# ControlModule.net
KiCad netlist of a schematic drawn in EAGLE
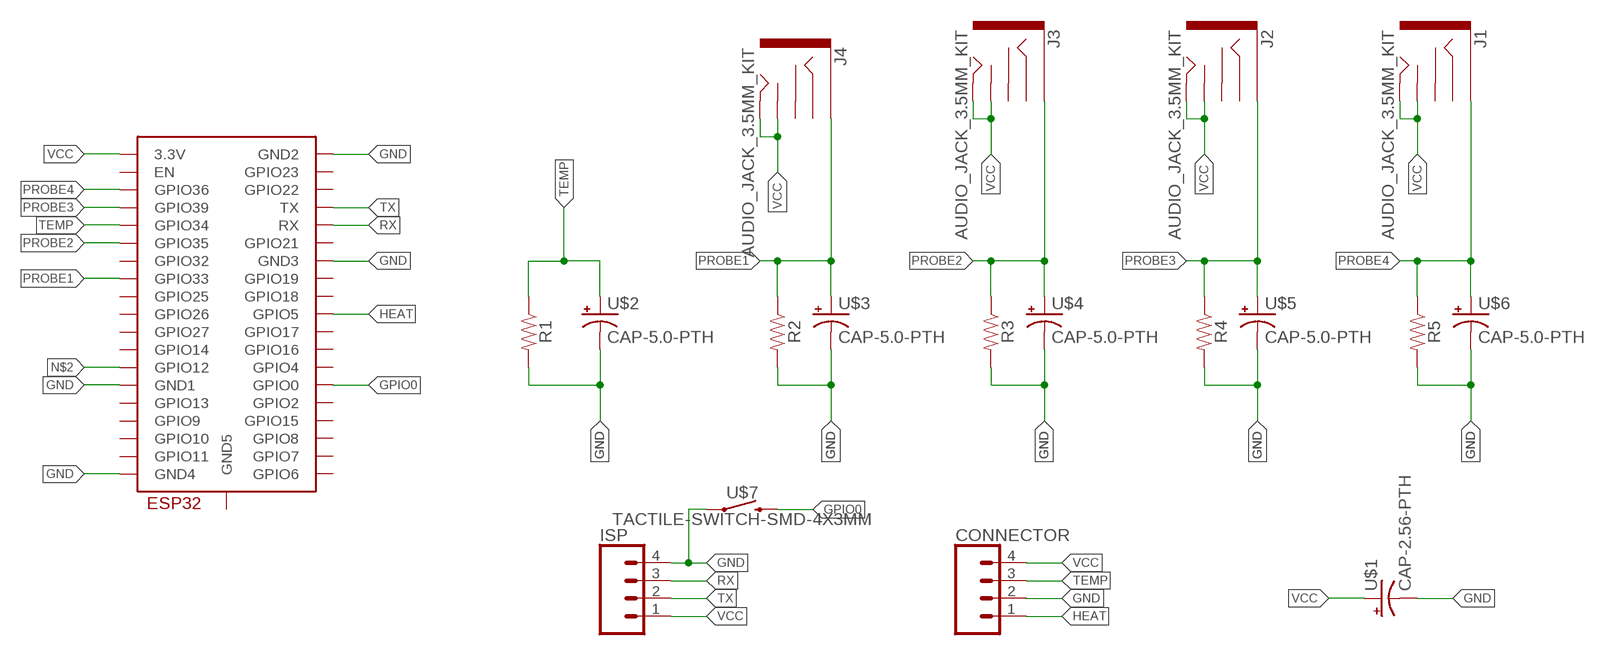
[diagram p0: schematic, sheet 1]

(export (version "E")
  (design (tool "Eeschema 10.0.6"))
  (components
    (comp (ref "CONNECTOR")
      (value "CONN_04PTH")
      (footprint "eagle-import:1X04")
      (libsource (lib "eagle-import") (part "CONN_04PTH"))
    )
    (comp (ref "ISP")
      (value "CONN_04PTH")
      (footprint "eagle-import:1X04")
      (libsource (lib "eagle-import") (part "CONN_04PTH"))
    )
    (comp (ref "J1")
      (value "AUDIO_JACK_3.5MM_KIT")
      (footprint "eagle-import:AUDIO-JACK-KIT")
      (libsource (lib "eagle-import") (part "AUDIO_JACK_3.5MM_KIT"))
    )
    (comp (ref "J2")
      (value "AUDIO_JACK_3.5MM_KIT")
      (footprint "eagle-import:AUDIO-JACK-KIT")
      (libsource (lib "eagle-import") (part "AUDIO_JACK_3.5MM_KIT"))
    )
    (comp (ref "J3")
      (value "AUDIO_JACK_3.5MM_KIT")
      (footprint "eagle-import:AUDIO-JACK-KIT")
      (libsource (lib "eagle-import") (part "AUDIO_JACK_3.5MM_KIT"))
    )
    (comp (ref "J4")
      (value "AUDIO_JACK_3.5MM_KIT")
      (footprint "eagle-import:AUDIO-JACK-KIT")
      (libsource (lib "eagle-import") (part "AUDIO_JACK_3.5MM_KIT"))
    )
    (comp (ref "R1")
      (value "RESISTOR0805")
      (footprint "eagle-import:0805")
      (libsource (lib "eagle-import") (part "RESISTOR0805"))
    )
    (comp (ref "R2")
      (value "RESISTOR0805")
      (footprint "eagle-import:0805")
      (libsource (lib "eagle-import") (part "RESISTOR0805"))
    )
    (comp (ref "R3")
      (value "RESISTOR0805")
      (footprint "eagle-import:0805")
      (libsource (lib "eagle-import") (part "RESISTOR0805"))
    )
    (comp (ref "R4")
      (value "RESISTOR0805")
      (footprint "eagle-import:0805")
      (libsource (lib "eagle-import") (part "RESISTOR0805"))
    )
    (comp (ref "R5")
      (value "RESISTOR0805")
      (footprint "eagle-import:0805")
      (libsource (lib "eagle-import") (part "RESISTOR0805"))
    )
    (comp (ref "U$1")
      (value "CAP-2.56-PTH")
      (footprint "eagle-import:CAP-PTH-2.5MM-5MM")
      (libsource (lib "eagle-import") (part "CAP-2.56-PTH"))
    )
    (comp (ref "U$2")
      (value "CAP-5.0-PTH")
      (footprint "eagle-import:CAP-PTH-5MM")
      (libsource (lib "eagle-import") (part "CAP-5.0-PTH"))
    )
    (comp (ref "U$3")
      (value "CAP-5.0-PTH")
      (footprint "eagle-import:CAP-PTH-5MM")
      (libsource (lib "eagle-import") (part "CAP-5.0-PTH"))
    )
    (comp (ref "U$4")
      (value "CAP-5.0-PTH")
      (footprint "eagle-import:CAP-PTH-5MM")
      (libsource (lib "eagle-import") (part "CAP-5.0-PTH"))
    )
    (comp (ref "U$5")
      (value "CAP-5.0-PTH")
      (footprint "eagle-import:CAP-PTH-5MM")
      (libsource (lib "eagle-import") (part "CAP-5.0-PTH"))
    )
    (comp (ref "U$6")
      (value "CAP-5.0-PTH")
      (footprint "eagle-import:CAP-PTH-5MM")
      (libsource (lib "eagle-import") (part "CAP-5.0-PTH"))
    )
    (comp (ref "U$7")
      (value "TACTILE-SWITCH-SMD-4X3MM")
      (footprint "eagle-import:TACTILE_SWITCH_SMD_4X3MM")
      (libsource (lib "eagle-import") (part "TACTILE-SWITCH-SMD-4X3MM"))
    )
    (comp (ref "U$8")
      (value "ESP32-WROOM")
      (footprint "eagle-import:ESP32-WROOM")
      (libsource (lib "eagle-import") (part "ESP32-WROOM"))
    )
  )
  (nets
    (net (code "1") (name "GND") (class "Default")
      (node (ref "CONNECTOR") (pin "2") (pinfunction "2_2") (pintype "passive"))
      (node (ref "ISP") (pin "4") (pinfunction "4_4") (pintype "passive"))
      (node (ref "R1") (pin "2") (pinfunction "2_2") (pintype "passive"))
      (node (ref "R2") (pin "2") (pinfunction "2_2") (pintype "passive"))
      (node (ref "R3") (pin "2") (pinfunction "2_2") (pintype "passive"))
      (node (ref "R4") (pin "2") (pinfunction "2_2") (pintype "passive"))
      (node (ref "R5") (pin "2") (pinfunction "2_2") (pintype "passive"))
      (node (ref "U$1") (pin "2") (pinfunction "-_2") (pintype "passive"))
      (node (ref "U$2") (pin "2") (pinfunction "-_2") (pintype "passive"))
      (node (ref "U$3") (pin "2") (pinfunction "-_2") (pintype "passive"))
      (node (ref "U$4") (pin "2") (pinfunction "-_2") (pintype "passive"))
      (node (ref "U$5") (pin "2") (pinfunction "-_2") (pintype "passive"))
      (node (ref "U$6") (pin "2") (pinfunction "-_2") (pintype "passive"))
      (node (ref "U$7") (pin "1") (pinfunction "1_1") (pintype "passive"))
      (node (ref "U$8") (pin "GND1") (pinfunction "GND1_GND1") (pintype "bidirectional"))
      (node (ref "U$8") (pin "GND2") (pinfunction "GND2_GND2") (pintype "bidirectional"))
      (node (ref "U$8") (pin "GND3") (pinfunction "GND3_GND3") (pintype "bidirectional"))
      (node (ref "U$8") (pin "GND4") (pinfunction "GND4_GND4") (pintype "bidirectional"))
    )
    (net (code "2") (name "GPIO0") (class "Default")
      (node (ref "U$7") (pin "2") (pinfunction "2_2") (pintype "passive"))
      (node (ref "U$8") (pin "IO0") (pinfunction "GPIO0_IO0") (pintype "bidirectional"))
    )
    (net (code "3") (name "HEAT") (class "Default")
      (node (ref "CONNECTOR") (pin "1") (pinfunction "1_1") (pintype "passive"))
      (node (ref "U$8") (pin "IO5") (pinfunction "GPIO5_IO5") (pintype "bidirectional"))
    )
    (net (code "4") (name "N$2") (class "Default")
      (node (ref "U$8") (pin "IO12") (pinfunction "GPIO12_IO12") (pintype "bidirectional"))
    )
    (net (code "5") (name "PROBE1") (class "Default")
      (node (ref "J4") (pin "SLEEVE") (pinfunction "SLEEVE_SLEEVE") (pintype "bidirectional"))
      (node (ref "R2") (pin "1") (pinfunction "1_1") (pintype "passive"))
      (node (ref "U$3") (pin "1") (pinfunction "+_1") (pintype "passive"))
      (node (ref "U$8") (pin "IO33") (pinfunction "GPIO33_IO33") (pintype "bidirectional"))
    )
    (net (code "6") (name "PROBE2") (class "Default")
      (node (ref "J3") (pin "SLEEVE") (pinfunction "SLEEVE_SLEEVE") (pintype "bidirectional"))
      (node (ref "R3") (pin "1") (pinfunction "1_1") (pintype "passive"))
      (node (ref "U$4") (pin "1") (pinfunction "+_1") (pintype "passive"))
      (node (ref "U$8") (pin "IO35") (pinfunction "GPIO35_IO35") (pintype "bidirectional"))
    )
    (net (code "7") (name "PROBE3") (class "Default")
      (node (ref "J2") (pin "SLEEVE") (pinfunction "SLEEVE_SLEEVE") (pintype "bidirectional"))
      (node (ref "R4") (pin "1") (pinfunction "1_1") (pintype "passive"))
      (node (ref "U$5") (pin "1") (pinfunction "+_1") (pintype "passive"))
      (node (ref "U$8") (pin "SENSOR_VN") (pinfunction "GPIO39_SENSOR_VN") (pintype "bidirectional"))
    )
    (net (code "8") (name "PROBE4") (class "Default")
      (node (ref "J1") (pin "SLEEVE") (pinfunction "SLEEVE_SLEEVE") (pintype "bidirectional"))
      (node (ref "R5") (pin "1") (pinfunction "1_1") (pintype "passive"))
      (node (ref "U$6") (pin "1") (pinfunction "+_1") (pintype "passive"))
      (node (ref "U$8") (pin "SENSOR_VP") (pinfunction "GPIO36_SENSOR_VP") (pintype "bidirectional"))
    )
    (net (code "9") (name "RX") (class "Default")
      (node (ref "ISP") (pin "3") (pinfunction "3_3") (pintype "passive"))
      (node (ref "U$8") (pin "RX") (pinfunction "RX_RX") (pintype "bidirectional"))
    )
    (net (code "10") (name "TEMP") (class "Default")
      (node (ref "CONNECTOR") (pin "3") (pinfunction "3_3") (pintype "passive"))
      (node (ref "R1") (pin "1") (pinfunction "1_1") (pintype "passive"))
      (node (ref "U$2") (pin "1") (pinfunction "+_1") (pintype "passive"))
      (node (ref "U$8") (pin "IO34") (pinfunction "GPIO34_IO34") (pintype "bidirectional"))
    )
    (net (code "11") (name "TX") (class "Default")
      (node (ref "ISP") (pin "2") (pinfunction "2_2") (pintype "passive"))
      (node (ref "U$8") (pin "TX") (pinfunction "TX_TX") (pintype "bidirectional"))
    )
    (net (code "12") (name "VCC") (class "Default")
      (node (ref "CONNECTOR") (pin "4") (pinfunction "4_4") (pintype "passive"))
      (node (ref "ISP") (pin "1") (pinfunction "1_1") (pintype "passive"))
      (node (ref "J1") (pin "TIP") (pinfunction "TIP_TIP") (pintype "bidirectional"))
      (node (ref "J1") (pin "TSH") (pinfunction "TSH_TSH") (pintype "bidirectional"))
      (node (ref "J2") (pin "TIP") (pinfunction "TIP_TIP") (pintype "bidirectional"))
      (node (ref "J2") (pin "TSH") (pinfunction "TSH_TSH") (pintype "bidirectional"))
      (node (ref "J3") (pin "TIP") (pinfunction "TIP_TIP") (pintype "bidirectional"))
      (node (ref "J3") (pin "TSH") (pinfunction "TSH_TSH") (pintype "bidirectional"))
      (node (ref "J4") (pin "TIP") (pinfunction "TIP_TIP") (pintype "bidirectional"))
      (node (ref "J4") (pin "TSH") (pinfunction "TSH_TSH") (pintype "bidirectional"))
      (node (ref "U$1") (pin "1") (pinfunction "+_1") (pintype "passive"))
      (node (ref "U$8") (pin "3V3") (pinfunction "3.3V_3V3") (pintype "bidirectional"))
    )
    (net (code "13") (name "unconnected-(J1-PadRING)") (class "Default")
      (node (ref "J1") (pin "RING") (pinfunction "RING_RING") (pintype "bidirectional"))
    )
    (net (code "14") (name "unconnected-(J1-PadRSH)") (class "Default")
      (node (ref "J1") (pin "RSH") (pinfunction "RSH_RSH") (pintype "bidirectional"))
    )
    (net (code "15") (name "unconnected-(J2-PadRING)") (class "Default")
      (node (ref "J2") (pin "RING") (pinfunction "RING_RING") (pintype "bidirectional"))
    )
    (net (code "16") (name "unconnected-(J2-PadRSH)") (class "Default")
      (node (ref "J2") (pin "RSH") (pinfunction "RSH_RSH") (pintype "bidirectional"))
    )
    (net (code "17") (name "unconnected-(J3-PadRING)") (class "Default")
      (node (ref "J3") (pin "RING") (pinfunction "RING_RING") (pintype "bidirectional"))
    )
    (net (code "18") (name "unconnected-(J3-PadRSH)") (class "Default")
      (node (ref "J3") (pin "RSH") (pinfunction "RSH_RSH") (pintype "bidirectional"))
    )
    (net (code "19") (name "unconnected-(J4-PadRING)") (class "Default")
      (node (ref "J4") (pin "RING") (pinfunction "RING_RING") (pintype "bidirectional"))
    )
    (net (code "20") (name "unconnected-(J4-PadRSH)") (class "Default")
      (node (ref "J4") (pin "RSH") (pinfunction "RSH_RSH") (pintype "bidirectional"))
    )
    (net (code "21") (name "unconnected-(U$8-GPIO2-PadIO2)") (class "Default")
      (node (ref "U$8") (pin "IO2") (pinfunction "GPIO2_IO2") (pintype "bidirectional"))
    )
    (net (code "22") (name "unconnected-(U$8-GPIO4-PadIO4)") (class "Default")
      (node (ref "U$8") (pin "IO4") (pinfunction "GPIO4_IO4") (pintype "bidirectional"))
    )
    (net (code "23") (name "unconnected-(U$8-GPIO6-PadCLK)") (class "Default")
      (node (ref "U$8") (pin "CLK") (pinfunction "GPIO6_CLK") (pintype "bidirectional"))
    )
    (net (code "24") (name "unconnected-(U$8-GPIO7-PadSD0)") (class "Default")
      (node (ref "U$8") (pin "SD0") (pinfunction "GPIO7_SD0") (pintype "bidirectional"))
    )
    (net (code "25") (name "unconnected-(U$8-GPIO8-PadSD1)") (class "Default")
      (node (ref "U$8") (pin "SD1") (pinfunction "GPIO8_SD1") (pintype "bidirectional"))
    )
    (net (code "26") (name "unconnected-(U$8-GPIO9-PadSD2)") (class "Default")
      (node (ref "U$8") (pin "SD2") (pinfunction "GPIO9_SD2") (pintype "bidirectional"))
    )
    (net (code "27") (name "unconnected-(U$8-GPIO10-PadSD3)") (class "Default")
      (node (ref "U$8") (pin "SD3") (pinfunction "GPIO10_SD3") (pintype "bidirectional"))
    )
    (net (code "28") (name "unconnected-(U$8-GPIO11-PadCMD)") (class "Default")
      (node (ref "U$8") (pin "CMD") (pinfunction "GPIO11_CMD") (pintype "bidirectional"))
    )
    (net (code "29") (name "unconnected-(U$8-GPIO13-PadIO13)") (class "Default")
      (node (ref "U$8") (pin "IO13") (pinfunction "GPIO13_IO13") (pintype "bidirectional"))
    )
    (net (code "30") (name "unconnected-(U$8-GPIO14-PadIO14)") (class "Default")
      (node (ref "U$8") (pin "IO14") (pinfunction "GPIO14_IO14") (pintype "bidirectional"))
    )
    (net (code "31") (name "unconnected-(U$8-GPIO15-PadIO15)") (class "Default")
      (node (ref "U$8") (pin "IO15") (pinfunction "GPIO15_IO15") (pintype "bidirectional"))
    )
    (net (code "32") (name "unconnected-(U$8-GPIO16-PadIO16)") (class "Default")
      (node (ref "U$8") (pin "IO16") (pinfunction "GPIO16_IO16") (pintype "bidirectional"))
    )
    (net (code "33") (name "unconnected-(U$8-GPIO17-PadIO17)") (class "Default")
      (node (ref "U$8") (pin "IO17") (pinfunction "GPIO17_IO17") (pintype "bidirectional"))
    )
    (net (code "34") (name "unconnected-(U$8-GPIO18-PadIO18)") (class "Default")
      (node (ref "U$8") (pin "IO18") (pinfunction "GPIO18_IO18") (pintype "bidirectional"))
    )
    (net (code "35") (name "unconnected-(U$8-GPIO19-PadIO19)") (class "Default")
      (node (ref "U$8") (pin "IO19") (pinfunction "GPIO19_IO19") (pintype "bidirectional"))
    )
    (net (code "36") (name "unconnected-(U$8-GPIO21-PadIO21)") (class "Default")
      (node (ref "U$8") (pin "IO21") (pinfunction "GPIO21_IO21") (pintype "bidirectional"))
    )
    (net (code "37") (name "unconnected-(U$8-GPIO22-PadIO22)") (class "Default")
      (node (ref "U$8") (pin "IO22") (pinfunction "GPIO22_IO22") (pintype "bidirectional"))
    )
    (net (code "38") (name "unconnected-(U$8-GPIO23-PadIO23)") (class "Default")
      (node (ref "U$8") (pin "IO23") (pinfunction "GPIO23_IO23") (pintype "bidirectional"))
    )
    (net (code "39") (name "unconnected-(U$8-GPIO25-PadIO25)") (class "Default")
      (node (ref "U$8") (pin "IO25") (pinfunction "GPIO25_IO25") (pintype "bidirectional"))
    )
    (net (code "40") (name "unconnected-(U$8-GPIO26-PadIO26)") (class "Default")
      (node (ref "U$8") (pin "IO26") (pinfunction "GPIO26_IO26") (pintype "bidirectional"))
    )
    (net (code "41") (name "unconnected-(U$8-GPIO27-PadIO27)") (class "Default")
      (node (ref "U$8") (pin "IO27") (pinfunction "GPIO27_IO27") (pintype "bidirectional"))
    )
    (net (code "42") (name "unconnected-(U$8-GPIO32-PadIO32)") (class "Default")
      (node (ref "U$8") (pin "IO32") (pinfunction "GPIO32_IO32") (pintype "bidirectional"))
    )
    (net (code "43") (name "unconnected-(U$8-PadEN)") (class "Default")
      (node (ref "U$8") (pin "EN") (pinfunction "EN_EN") (pintype "bidirectional"))
    )
    (net (code "44") (name "unconnected-(U$8-PadGND5)") (class "Default")
      (node (ref "U$8") (pin "GND5") (pinfunction "GND5_GND5") (pintype "bidirectional"))
    )
  )
)
